# AS3364_DG412_bus_mixer_v1_0_copy.net
KiCad netlist of a schematic drawn in EAGLE
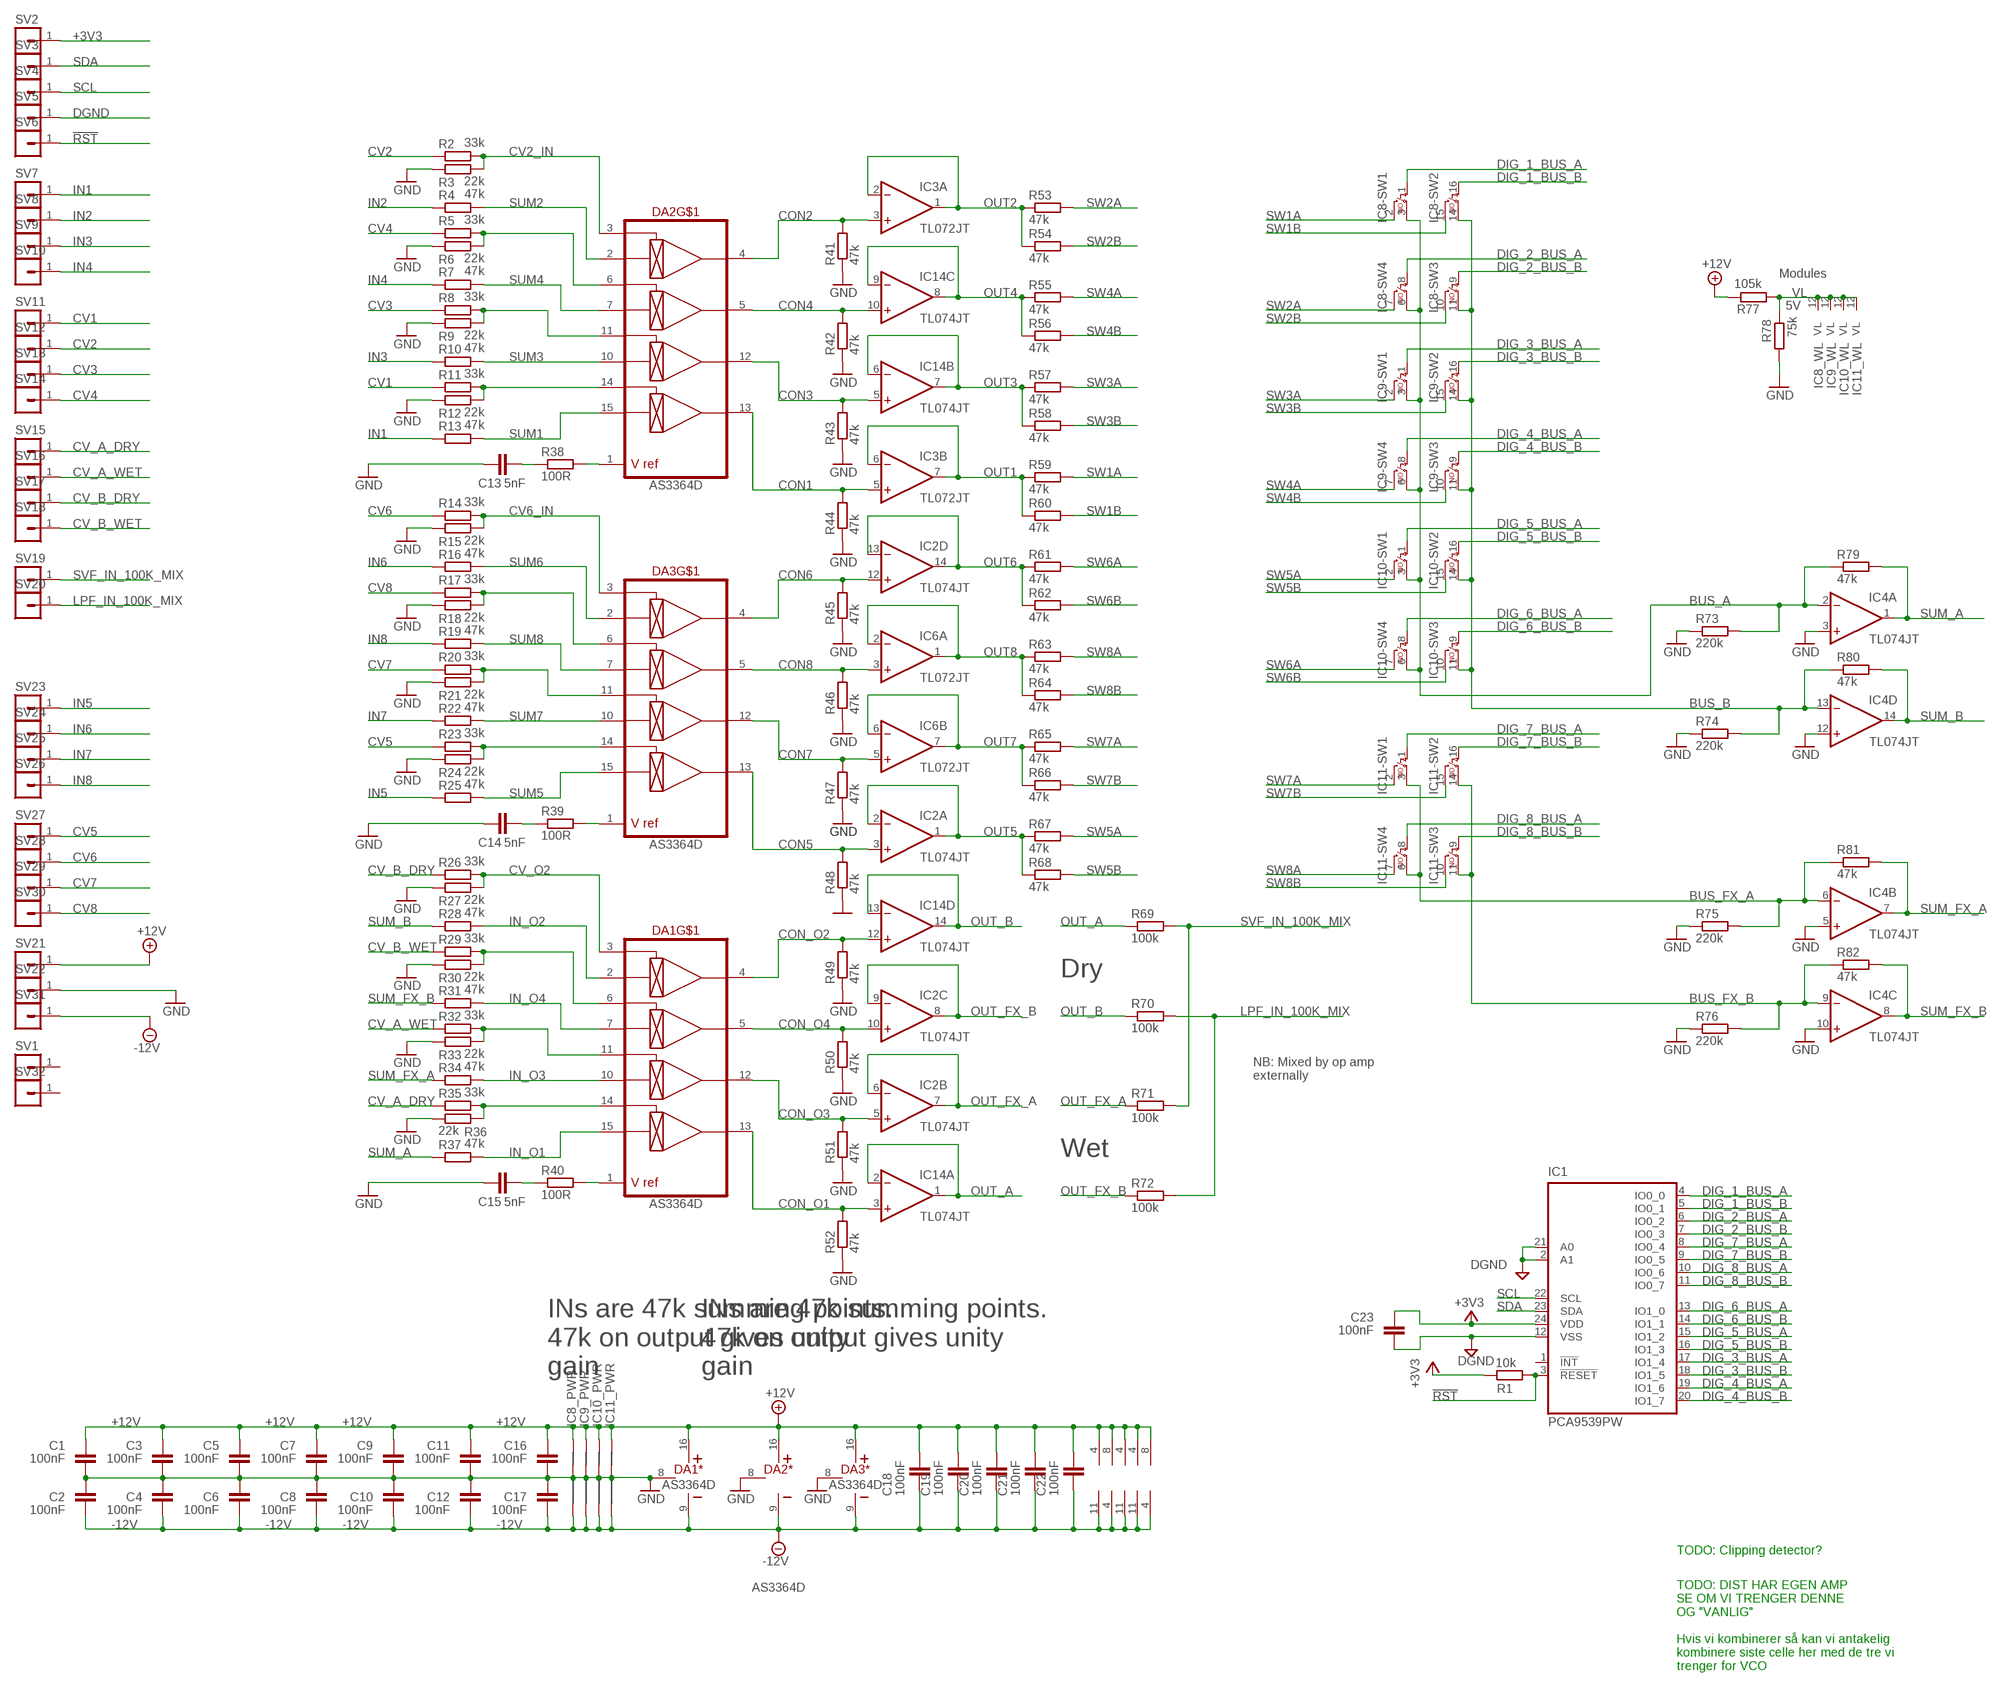
[diagram p0: schematic, sheet 1]

(export (version "E")
  (design (tool "Eeschema 10.0.6"))
  (components
    (comp (ref "C1")
      (value "100nF")
      (footprint "eagle-import:C0402")
      (libsource (lib "eagle-import") (part "C-EUC0402"))
    )
    (comp (ref "C2")
      (value "100nF")
      (footprint "eagle-import:C0402")
      (libsource (lib "eagle-import") (part "C-EUC0402"))
    )
    (comp (ref "C3")
      (value "100nF")
      (footprint "eagle-import:C0402")
      (libsource (lib "eagle-import") (part "C-EUC0402"))
    )
    (comp (ref "C4")
      (value "100nF")
      (footprint "eagle-import:C0402")
      (libsource (lib "eagle-import") (part "C-EUC0402"))
    )
    (comp (ref "C5")
      (value "100nF")
      (footprint "eagle-import:C0402")
      (libsource (lib "eagle-import") (part "C-EUC0402"))
    )
    (comp (ref "C6")
      (value "100nF")
      (footprint "eagle-import:C0402")
      (libsource (lib "eagle-import") (part "C-EUC0402"))
    )
    (comp (ref "C7")
      (value "100nF")
      (footprint "eagle-import:C0402")
      (libsource (lib "eagle-import") (part "C-EUC0402"))
    )
    (comp (ref "C8")
      (value "100nF")
      (footprint "eagle-import:C0402")
      (libsource (lib "eagle-import") (part "C-EUC0402"))
    )
    (comp (ref "C9")
      (value "100nF")
      (footprint "eagle-import:C0402")
      (libsource (lib "eagle-import") (part "C-EUC0402"))
    )
    (comp (ref "C10")
      (value "100nF")
      (footprint "eagle-import:C0402")
      (libsource (lib "eagle-import") (part "C-EUC0402"))
    )
    (comp (ref "C11")
      (value "100nF")
      (footprint "eagle-import:C0402")
      (libsource (lib "eagle-import") (part "C-EUC0402"))
    )
    (comp (ref "C12")
      (value "100nF")
      (footprint "eagle-import:C0402")
      (libsource (lib "eagle-import") (part "C-EUC0402"))
    )
    (comp (ref "C13")
      (value "5nF")
      (footprint "eagle-import:C0402")
      (libsource (lib "eagle-import") (part "C-EUC0402"))
    )
    (comp (ref "C14")
      (value "5nF")
      (footprint "eagle-import:C0402")
      (libsource (lib "eagle-import") (part "C-EUC0402"))
    )
    (comp (ref "C15")
      (value "5nF")
      (footprint "eagle-import:C0402")
      (libsource (lib "eagle-import") (part "C-EUC0402"))
    )
    (comp (ref "C16")
      (value "100nF")
      (footprint "eagle-import:C0402")
      (libsource (lib "eagle-import") (part "C-EUC0402"))
    )
    (comp (ref "C17")
      (value "100nF")
      (footprint "eagle-import:C0402")
      (libsource (lib "eagle-import") (part "C-EUC0402"))
    )
    (comp (ref "C18")
      (value "100nF")
      (footprint "eagle-import:C0402")
      (libsource (lib "eagle-import") (part "C-EUC0402"))
    )
    (comp (ref "C19")
      (value "100nF")
      (footprint "eagle-import:C0402")
      (libsource (lib "eagle-import") (part "C-EUC0402"))
    )
    (comp (ref "C20")
      (value "100nF")
      (footprint "eagle-import:C0402")
      (libsource (lib "eagle-import") (part "C-EUC0402"))
    )
    (comp (ref "C21")
      (value "100nF")
      (footprint "eagle-import:C0402")
      (libsource (lib "eagle-import") (part "C-EUC0402"))
    )
    (comp (ref "C22")
      (value "100nF")
      (footprint "eagle-import:C0402")
      (libsource (lib "eagle-import") (part "C-EUC0402"))
    )
    (comp (ref "C23")
      (value "100nF")
      (footprint "eagle-import:C0402")
      (libsource (lib "eagle-import") (part "C-EUC0402"))
    )
    (comp (ref "DA1")
      (value "AS3364D")
      (footprint "eagle-import:DIL16J")
      (libsource (lib "eagle-import") (part "AS3364D"))
    )
    (comp (ref "DA2")
      (value "AS3364D")
      (footprint "eagle-import:DIL16J")
      (libsource (lib "eagle-import") (part "AS3364D"))
    )
    (comp (ref "DA3")
      (value "AS3364D")
      (footprint "eagle-import:DIL16J")
      (libsource (lib "eagle-import") (part "AS3364D"))
    )
    (comp (ref "IC1")
      (value "PCA9539PW")
      (footprint "eagle-import:TSSOP24J")
      (libsource (lib "eagle-import") (part "PCA9539PW"))
    )
    (comp (ref "IC2")
      (value "TL074JT")
      (footprint "eagle-import:TSSOP14J")
      (libsource (lib "eagle-import") (part "TL074JT"))
    )
    (comp (ref "IC3")
      (value "TL072JT")
      (footprint "eagle-import:TSSOP8J")
      (libsource (lib "eagle-import") (part "TL072JT"))
    )
    (comp (ref "IC4")
      (value "TL074JT")
      (footprint "eagle-import:TSSOP14J")
      (libsource (lib "eagle-import") (part "TL074JT"))
    )
    (comp (ref "IC6")
      (value "TL072JT")
      (footprint "eagle-import:TSSOP8J")
      (libsource (lib "eagle-import") (part "TL072JT"))
    )
    (comp (ref "IC8")
      (value "DG412-J")
      (footprint "eagle-import:DIL16J")
      (libsource (lib "eagle-import") (part "DG412-J"))
    )
    (comp (ref "IC9")
      (value "DG412-J")
      (footprint "eagle-import:DIL16J")
      (libsource (lib "eagle-import") (part "DG412-J"))
    )
    (comp (ref "IC10")
      (value "DG412-J")
      (footprint "eagle-import:DIL16J")
      (libsource (lib "eagle-import") (part "DG412-J"))
    )
    (comp (ref "IC11")
      (value "DG412-J")
      (footprint "eagle-import:DIL16J")
      (libsource (lib "eagle-import") (part "DG412-J"))
    )
    (comp (ref "IC14")
      (value "TL074JT")
      (footprint "eagle-import:TSSOP14J")
      (libsource (lib "eagle-import") (part "TL074JT"))
    )
    (comp (ref "R1")
      (value "10k")
      (footprint "eagle-import:R0402")
      (libsource (lib "eagle-import") (part "R-EU_R0402"))
    )
    (comp (ref "R2")
      (value "33k")
      (footprint "eagle-import:R0402")
      (libsource (lib "eagle-import") (part "R-EU_R0402"))
    )
    (comp (ref "R3")
      (value "22k")
      (footprint "eagle-import:R0402")
      (libsource (lib "eagle-import") (part "R-EU_R0402"))
    )
    (comp (ref "R4")
      (value "47k")
      (footprint "eagle-import:R0402")
      (libsource (lib "eagle-import") (part "R-EU_R0402"))
    )
    (comp (ref "R5")
      (value "33k")
      (footprint "eagle-import:R0402")
      (libsource (lib "eagle-import") (part "R-EU_R0402"))
    )
    (comp (ref "R6")
      (value "22k")
      (footprint "eagle-import:R0402")
      (libsource (lib "eagle-import") (part "R-EU_R0402"))
    )
    (comp (ref "R7")
      (value "47k")
      (footprint "eagle-import:R0402")
      (libsource (lib "eagle-import") (part "R-EU_R0402"))
    )
    (comp (ref "R8")
      (value "33k")
      (footprint "eagle-import:R0402")
      (libsource (lib "eagle-import") (part "R-EU_R0402"))
    )
    (comp (ref "R9")
      (value "22k")
      (footprint "eagle-import:R0402")
      (libsource (lib "eagle-import") (part "R-EU_R0402"))
    )
    (comp (ref "R10")
      (value "47k")
      (footprint "eagle-import:R0402")
      (libsource (lib "eagle-import") (part "R-EU_R0402"))
    )
    (comp (ref "R11")
      (value "33k")
      (footprint "eagle-import:R0402")
      (libsource (lib "eagle-import") (part "R-EU_R0402"))
    )
    (comp (ref "R12")
      (value "22k")
      (footprint "eagle-import:R0402")
      (libsource (lib "eagle-import") (part "R-EU_R0402"))
    )
    (comp (ref "R13")
      (value "47k")
      (footprint "eagle-import:R0402")
      (libsource (lib "eagle-import") (part "R-EU_R0402"))
    )
    (comp (ref "R14")
      (value "33k")
      (footprint "eagle-import:R0402")
      (libsource (lib "eagle-import") (part "R-EU_R0402"))
    )
    (comp (ref "R15")
      (value "22k")
      (footprint "eagle-import:R0402")
      (libsource (lib "eagle-import") (part "R-EU_R0402"))
    )
    (comp (ref "R16")
      (value "47k")
      (footprint "eagle-import:R0402")
      (libsource (lib "eagle-import") (part "R-EU_R0402"))
    )
    (comp (ref "R17")
      (value "33k")
      (footprint "eagle-import:R0402")
      (libsource (lib "eagle-import") (part "R-EU_R0402"))
    )
    (comp (ref "R18")
      (value "22k")
      (footprint "eagle-import:R0402")
      (libsource (lib "eagle-import") (part "R-EU_R0402"))
    )
    (comp (ref "R19")
      (value "47k")
      (footprint "eagle-import:R0402")
      (libsource (lib "eagle-import") (part "R-EU_R0402"))
    )
    (comp (ref "R20")
      (value "33k")
      (footprint "eagle-import:R0402")
      (libsource (lib "eagle-import") (part "R-EU_R0402"))
    )
    (comp (ref "R21")
      (value "22k")
      (footprint "eagle-import:R0402")
      (libsource (lib "eagle-import") (part "R-EU_R0402"))
    )
    (comp (ref "R22")
      (value "47k")
      (footprint "eagle-import:R0402")
      (libsource (lib "eagle-import") (part "R-EU_R0402"))
    )
    (comp (ref "R23")
      (value "33k")
      (footprint "eagle-import:R0402")
      (libsource (lib "eagle-import") (part "R-EU_R0402"))
    )
    (comp (ref "R24")
      (value "22k")
      (footprint "eagle-import:R0402")
      (libsource (lib "eagle-import") (part "R-EU_R0402"))
    )
    (comp (ref "R25")
      (value "47k")
      (footprint "eagle-import:R0402")
      (libsource (lib "eagle-import") (part "R-EU_R0402"))
    )
    (comp (ref "R26")
      (value "33k")
      (footprint "eagle-import:R0402")
      (libsource (lib "eagle-import") (part "R-EU_R0402"))
    )
    (comp (ref "R27")
      (value "22k")
      (footprint "eagle-import:R0402")
      (libsource (lib "eagle-import") (part "R-EU_R0402"))
    )
    (comp (ref "R28")
      (value "47k")
      (footprint "eagle-import:R0402")
      (libsource (lib "eagle-import") (part "R-EU_R0402"))
    )
    (comp (ref "R29")
      (value "33k")
      (footprint "eagle-import:R0402")
      (libsource (lib "eagle-import") (part "R-EU_R0402"))
    )
    (comp (ref "R30")
      (value "22k")
      (footprint "eagle-import:R0402")
      (libsource (lib "eagle-import") (part "R-EU_R0402"))
    )
    (comp (ref "R31")
      (value "47k")
      (footprint "eagle-import:R0402")
      (libsource (lib "eagle-import") (part "R-EU_R0402"))
    )
    (comp (ref "R32")
      (value "33k")
      (footprint "eagle-import:R0402")
      (libsource (lib "eagle-import") (part "R-EU_R0402"))
    )
    (comp (ref "R33")
      (value "22k")
      (footprint "eagle-import:R0402")
      (libsource (lib "eagle-import") (part "R-EU_R0402"))
    )
    (comp (ref "R34")
      (value "47k")
      (footprint "eagle-import:R0402")
      (libsource (lib "eagle-import") (part "R-EU_R0402"))
    )
    (comp (ref "R35")
      (value "33k")
      (footprint "eagle-import:R0402")
      (libsource (lib "eagle-import") (part "R-EU_R0402"))
    )
    (comp (ref "R36")
      (value "22k")
      (footprint "eagle-import:R0402")
      (libsource (lib "eagle-import") (part "R-EU_R0402"))
    )
    (comp (ref "R37")
      (value "47k")
      (footprint "eagle-import:R0402")
      (libsource (lib "eagle-import") (part "R-EU_R0402"))
    )
    (comp (ref "R38")
      (value "100R")
      (footprint "eagle-import:R0402")
      (libsource (lib "eagle-import") (part "R-EU_R0402"))
    )
    (comp (ref "R39")
      (value "100R")
      (footprint "eagle-import:R0402")
      (libsource (lib "eagle-import") (part "R-EU_R0402"))
    )
    (comp (ref "R40")
      (value "100R")
      (footprint "eagle-import:R0402")
      (libsource (lib "eagle-import") (part "R-EU_R0402"))
    )
    (comp (ref "R41")
      (value "47k")
      (footprint "eagle-import:R0402")
      (libsource (lib "eagle-import") (part "R-EU_R0402"))
    )
    (comp (ref "R42")
      (value "47k")
      (footprint "eagle-import:R0402")
      (libsource (lib "eagle-import") (part "R-EU_R0402"))
    )
    (comp (ref "R43")
      (value "47k")
      (footprint "eagle-import:R0402")
      (libsource (lib "eagle-import") (part "R-EU_R0402"))
    )
    (comp (ref "R44")
      (value "47k")
      (footprint "eagle-import:R0402")
      (libsource (lib "eagle-import") (part "R-EU_R0402"))
    )
    (comp (ref "R45")
      (value "47k")
      (footprint "eagle-import:R0402")
      (libsource (lib "eagle-import") (part "R-EU_R0402"))
    )
    (comp (ref "R46")
      (value "47k")
      (footprint "eagle-import:R0402")
      (libsource (lib "eagle-import") (part "R-EU_R0402"))
    )
    (comp (ref "R47")
      (value "47k")
      (footprint "eagle-import:R0402")
      (libsource (lib "eagle-import") (part "R-EU_R0402"))
    )
    (comp (ref "R48")
      (value "47k")
      (footprint "eagle-import:R0402")
      (libsource (lib "eagle-import") (part "R-EU_R0402"))
    )
    (comp (ref "R49")
      (value "47k")
      (footprint "eagle-import:R0402")
      (libsource (lib "eagle-import") (part "R-EU_R0402"))
    )
    (comp (ref "R50")
      (value "47k")
      (footprint "eagle-import:R0402")
      (libsource (lib "eagle-import") (part "R-EU_R0402"))
    )
    (comp (ref "R51")
      (value "47k")
      (footprint "eagle-import:R0402")
      (libsource (lib "eagle-import") (part "R-EU_R0402"))
    )
    (comp (ref "R52")
      (value "47k")
      (footprint "eagle-import:R0402")
      (libsource (lib "eagle-import") (part "R-EU_R0402"))
    )
    (comp (ref "R53")
      (value "47k")
      (footprint "eagle-import:R0402")
      (libsource (lib "eagle-import") (part "R-EU_R0402"))
    )
    (comp (ref "R54")
      (value "47k")
      (footprint "eagle-import:R0402")
      (libsource (lib "eagle-import") (part "R-EU_R0402"))
    )
    (comp (ref "R55")
      (value "47k")
      (footprint "eagle-import:R0402")
      (libsource (lib "eagle-import") (part "R-EU_R0402"))
    )
    (comp (ref "R56")
      (value "47k")
      (footprint "eagle-import:R0402")
      (libsource (lib "eagle-import") (part "R-EU_R0402"))
    )
    (comp (ref "R57")
      (value "47k")
      (footprint "eagle-import:R0402")
      (libsource (lib "eagle-import") (part "R-EU_R0402"))
    )
    (comp (ref "R58")
      (value "47k")
      (footprint "eagle-import:R0402")
      (libsource (lib "eagle-import") (part "R-EU_R0402"))
    )
    (comp (ref "R59")
      (value "47k")
      (footprint "eagle-import:R0402")
      (libsource (lib "eagle-import") (part "R-EU_R0402"))
    )
    (comp (ref "R60")
      (value "47k")
      (footprint "eagle-import:R0402")
      (libsource (lib "eagle-import") (part "R-EU_R0402"))
    )
    (comp (ref "R61")
      (value "47k")
      (footprint "eagle-import:R0402")
      (libsource (lib "eagle-import") (part "R-EU_R0402"))
    )
    (comp (ref "R62")
      (value "47k")
      (footprint "eagle-import:R0402")
      (libsource (lib "eagle-import") (part "R-EU_R0402"))
    )
    (comp (ref "R63")
      (value "47k")
      (footprint "eagle-import:R0402")
      (libsource (lib "eagle-import") (part "R-EU_R0402"))
    )
    (comp (ref "R64")
      (value "47k")
      (footprint "eagle-import:R0402")
      (libsource (lib "eagle-import") (part "R-EU_R0402"))
    )
    (comp (ref "R65")
      (value "47k")
      (footprint "eagle-import:R0402")
      (libsource (lib "eagle-import") (part "R-EU_R0402"))
    )
    (comp (ref "R66")
      (value "47k")
      (footprint "eagle-import:R0402")
      (libsource (lib "eagle-import") (part "R-EU_R0402"))
    )
    (comp (ref "R67")
      (value "47k")
      (footprint "eagle-import:R0402")
      (libsource (lib "eagle-import") (part "R-EU_R0402"))
    )
    (comp (ref "R68")
      (value "47k")
      (footprint "eagle-import:R0402")
      (libsource (lib "eagle-import") (part "R-EU_R0402"))
    )
    (comp (ref "R69")
      (value "100k")
      (footprint "eagle-import:R0402")
      (libsource (lib "eagle-import") (part "R-EU_R0402"))
    )
    (comp (ref "R70")
      (value "100k")
      (footprint "eagle-import:R0402")
      (libsource (lib "eagle-import") (part "R-EU_R0402"))
    )
    (comp (ref "R71")
      (value "100k")
      (footprint "eagle-import:R0402")
      (libsource (lib "eagle-import") (part "R-EU_R0402"))
    )
    (comp (ref "R72")
      (value "100k")
      (footprint "eagle-import:R0402")
      (libsource (lib "eagle-import") (part "R-EU_R0402"))
    )
    (comp (ref "R73")
      (value "220k")
      (footprint "eagle-import:R0402")
      (libsource (lib "eagle-import") (part "R-EU_R0402"))
    )
    (comp (ref "R74")
      (value "220k")
      (footprint "eagle-import:R0402")
      (libsource (lib "eagle-import") (part "R-EU_R0402"))
    )
    (comp (ref "R75")
      (value "220k")
      (footprint "eagle-import:R0402")
      (libsource (lib "eagle-import") (part "R-EU_R0402"))
    )
    (comp (ref "R76")
      (value "220k")
      (footprint "eagle-import:R0402")
      (libsource (lib "eagle-import") (part "R-EU_R0402"))
    )
    (comp (ref "R77")
      (value "105k")
      (footprint "eagle-import:R0402")
      (libsource (lib "eagle-import") (part "R-EU_R0402"))
    )
    (comp (ref "R78")
      (value "75k")
      (footprint "eagle-import:R0402")
      (libsource (lib "eagle-import") (part "R-EU_R0402"))
    )
    (comp (ref "R79")
      (value "47k")
      (footprint "eagle-import:R0402")
      (libsource (lib "eagle-import") (part "R-EU_R0402"))
    )
    (comp (ref "R80")
      (value "47k")
      (footprint "eagle-import:R0402")
      (libsource (lib "eagle-import") (part "R-EU_R0402"))
    )
    (comp (ref "R81")
      (value "47k")
      (footprint "eagle-import:R0402")
      (libsource (lib "eagle-import") (part "R-EU_R0402"))
    )
    (comp (ref "R82")
      (value "47k")
      (footprint "eagle-import:R0402")
      (libsource (lib "eagle-import") (part "R-EU_R0402"))
    )
    (comp (ref "SV1")
      (value "MA01-1JP")
      (footprint "eagle-import:SIP-PIN01-1J")
      (libsource (lib "eagle-import") (part "MA01-1JP"))
    )
    (comp (ref "SV2")
      (value "MA01-1JP")
      (footprint "eagle-import:SIP-PIN01-1J")
      (libsource (lib "eagle-import") (part "MA01-1JP"))
    )
    (comp (ref "SV3")
      (value "MA01-1JP")
      (footprint "eagle-import:SIP-PIN01-1J")
      (libsource (lib "eagle-import") (part "MA01-1JP"))
    )
    (comp (ref "SV4")
      (value "MA01-1JP")
      (footprint "eagle-import:SIP-PIN01-1J")
      (libsource (lib "eagle-import") (part "MA01-1JP"))
    )
    (comp (ref "SV5")
      (value "MA01-1JP")
      (footprint "eagle-import:SIP-PIN01-1J")
      (libsource (lib "eagle-import") (part "MA01-1JP"))
    )
    (comp (ref "SV6")
      (value "MA01-1JP")
      (footprint "eagle-import:SIP-PIN01-1J")
      (libsource (lib "eagle-import") (part "MA01-1JP"))
    )
    (comp (ref "SV7")
      (value "MA01-1JP")
      (footprint "eagle-import:SIP-PIN01-1J")
      (libsource (lib "eagle-import") (part "MA01-1JP"))
    )
    (comp (ref "SV8")
      (value "MA01-1JP")
      (footprint "eagle-import:SIP-PIN01-1J")
      (libsource (lib "eagle-import") (part "MA01-1JP"))
    )
    (comp (ref "SV9")
      (value "MA01-1JP")
      (footprint "eagle-import:SIP-PIN01-1J")
      (libsource (lib "eagle-import") (part "MA01-1JP"))
    )
    (comp (ref "SV10")
      (value "MA01-1JP")
      (footprint "eagle-import:SIP-PIN01-1J")
      (libsource (lib "eagle-import") (part "MA01-1JP"))
    )
    (comp (ref "SV11")
      (value "MA01-1JP")
      (footprint "eagle-import:SIP-PIN01-1J")
      (libsource (lib "eagle-import") (part "MA01-1JP"))
    )
    (comp (ref "SV12")
      (value "MA01-1JP")
      (footprint "eagle-import:SIP-PIN01-1J")
      (libsource (lib "eagle-import") (part "MA01-1JP"))
    )
    (comp (ref "SV13")
      (value "MA01-1JP")
      (footprint "eagle-import:SIP-PIN01-1J")
      (libsource (lib "eagle-import") (part "MA01-1JP"))
    )
    (comp (ref "SV14")
      (value "MA01-1JP")
      (footprint "eagle-import:SIP-PIN01-1J")
      (libsource (lib "eagle-import") (part "MA01-1JP"))
    )
    (comp (ref "SV15")
      (value "MA01-1JP")
      (footprint "eagle-import:SIP-PIN01-1J")
      (libsource (lib "eagle-import") (part "MA01-1JP"))
    )
    (comp (ref "SV16")
      (value "MA01-1JP")
      (footprint "eagle-import:SIP-PIN01-1J")
      (libsource (lib "eagle-import") (part "MA01-1JP"))
    )
    (comp (ref "SV17")
      (value "MA01-1JP")
      (footprint "eagle-import:SIP-PIN01-1J")
      (libsource (lib "eagle-import") (part "MA01-1JP"))
    )
    (comp (ref "SV18")
      (value "MA01-1JP")
      (footprint "eagle-import:SIP-PIN01-1J")
      (libsource (lib "eagle-import") (part "MA01-1JP"))
    )
    (comp (ref "SV19")
      (value "MA01-1JP")
      (footprint "eagle-import:SIP-PIN01-1J")
      (libsource (lib "eagle-import") (part "MA01-1JP"))
    )
    (comp (ref "SV20")
      (value "MA01-1JP")
      (footprint "eagle-import:SIP-PIN01-1J")
      (libsource (lib "eagle-import") (part "MA01-1JP"))
    )
    (comp (ref "SV21")
      (value "MA01-1JP")
      (footprint "eagle-import:SIP-PIN01-1J")
      (libsource (lib "eagle-import") (part "MA01-1JP"))
    )
    (comp (ref "SV22")
      (value "MA01-1JP")
      (footprint "eagle-import:SIP-PIN01-1J")
      (libsource (lib "eagle-import") (part "MA01-1JP"))
    )
    (comp (ref "SV23")
      (value "MA01-1JP")
      (footprint "eagle-import:SIP-PIN01-1J")
      (libsource (lib "eagle-import") (part "MA01-1JP"))
    )
    (comp (ref "SV24")
      (value "MA01-1JP")
      (footprint "eagle-import:SIP-PIN01-1J")
      (libsource (lib "eagle-import") (part "MA01-1JP"))
    )
    (comp (ref "SV25")
      (value "MA01-1JP")
      (footprint "eagle-import:SIP-PIN01-1J")
      (libsource (lib "eagle-import") (part "MA01-1JP"))
    )
    (comp (ref "SV26")
      (value "MA01-1JP")
      (footprint "eagle-import:SIP-PIN01-1J")
      (libsource (lib "eagle-import") (part "MA01-1JP"))
    )
    (comp (ref "SV27")
      (value "MA01-1JP")
      (footprint "eagle-import:SIP-PIN01-1J")
      (libsource (lib "eagle-import") (part "MA01-1JP"))
    )
    (comp (ref "SV28")
      (value "MA01-1JP")
      (footprint "eagle-import:SIP-PIN01-1J")
      (libsource (lib "eagle-import") (part "MA01-1JP"))
    )
    (comp (ref "SV29")
      (value "MA01-1JP")
      (footprint "eagle-import:SIP-PIN01-1J")
      (libsource (lib "eagle-import") (part "MA01-1JP"))
    )
    (comp (ref "SV30")
      (value "MA01-1JP")
      (footprint "eagle-import:SIP-PIN01-1J")
      (libsource (lib "eagle-import") (part "MA01-1JP"))
    )
    (comp (ref "SV31")
      (value "MA01-1JP")
      (footprint "eagle-import:SIP-PIN01-1J")
      (libsource (lib "eagle-import") (part "MA01-1JP"))
    )
    (comp (ref "SV32")
      (value "MA01-1JP")
      (footprint "eagle-import:SIP-PIN01-1J")
      (libsource (lib "eagle-import") (part "MA01-1JP"))
    )
  )
  (nets
    (net (code "1") (name "+3V3") (class "Default")
      (node (ref "C23") (pin "2") (pinfunction "2_2") (pintype "passive"))
      (node (ref "IC1") (pin "24") (pinfunction "VDD_24") (pintype "power_in"))
      (node (ref "R1") (pin "1") (pinfunction "1_1") (pintype "passive"))
      (node (ref "SV2") (pin "1") (pinfunction "1_1") (pintype "passive"))
    )
    (net (code "2") (name "+12V") (class "Default")
      (node (ref "C1") (pin "2") (pinfunction "2_2") (pintype "passive"))
      (node (ref "C11") (pin "2") (pinfunction "2_2") (pintype "passive"))
      (node (ref "C16") (pin "2") (pinfunction "2_2") (pintype "passive"))
      (node (ref "C18") (pin "2") (pinfunction "2_2") (pintype "passive"))
      (node (ref "C19") (pin "2") (pinfunction "2_2") (pintype "passive"))
      (node (ref "C20") (pin "2") (pinfunction "2_2") (pintype "passive"))
      (node (ref "C21") (pin "2") (pinfunction "2_2") (pintype "passive"))
      (node (ref "C22") (pin "2") (pinfunction "2_2") (pintype "passive"))
      (node (ref "C3") (pin "2") (pinfunction "2_2") (pintype "passive"))
      (node (ref "C5") (pin "2") (pinfunction "2_2") (pintype "passive"))
      (node (ref "C7") (pin "2") (pinfunction "2_2") (pintype "passive"))
      (node (ref "C9") (pin "2") (pinfunction "2_2") (pintype "passive"))
      (node (ref "DA1") (pin "16") (pinfunction "V+_16") (pintype "power_in"))
      (node (ref "DA2") (pin "16") (pinfunction "V+_16") (pintype "power_in"))
      (node (ref "DA3") (pin "16") (pinfunction "V+_16") (pintype "power_in"))
      (node (ref "IC10") (pin "13") (pinfunction "+15V_13") (pintype "power_in"))
      (node (ref "IC11") (pin "13") (pinfunction "+15V_13") (pintype "power_in"))
      (node (ref "IC14") (pin "4") (pinfunction "V+_4") (pintype "power_in"))
      (node (ref "IC2") (pin "4") (pinfunction "V+_4") (pintype "power_in"))
      (node (ref "IC3") (pin "8") (pinfunction "V+_8") (pintype "power_in"))
      (node (ref "IC4") (pin "4") (pinfunction "V+_4") (pintype "power_in"))
      (node (ref "IC6") (pin "8") (pinfunction "V+_8") (pintype "power_in"))
      (node (ref "IC8") (pin "13") (pinfunction "+15V_13") (pintype "power_in"))
      (node (ref "IC9") (pin "13") (pinfunction "+15V_13") (pintype "power_in"))
      (node (ref "R77") (pin "1") (pinfunction "1_1") (pintype "passive"))
      (node (ref "SV21") (pin "1") (pinfunction "1_1") (pintype "passive"))
    )
    (net (code "3") (name "-12V") (class "Default")
      (node (ref "C10") (pin "1") (pinfunction "1_1") (pintype "passive"))
      (node (ref "C12") (pin "1") (pinfunction "1_1") (pintype "passive"))
      (node (ref "C17") (pin "1") (pinfunction "1_1") (pintype "passive"))
      (node (ref "C18") (pin "1") (pinfunction "1_1") (pintype "passive"))
      (node (ref "C19") (pin "1") (pinfunction "1_1") (pintype "passive"))
      (node (ref "C2") (pin "1") (pinfunction "1_1") (pintype "passive"))
      (node (ref "C20") (pin "1") (pinfunction "1_1") (pintype "passive"))
      (node (ref "C21") (pin "1") (pinfunction "1_1") (pintype "passive"))
      (node (ref "C22") (pin "1") (pinfunction "1_1") (pintype "passive"))
      (node (ref "C4") (pin "1") (pinfunction "1_1") (pintype "passive"))
      (node (ref "C6") (pin "1") (pinfunction "1_1") (pintype "passive"))
      (node (ref "C8") (pin "1") (pinfunction "1_1") (pintype "passive"))
      (node (ref "DA1") (pin "9") (pinfunction "V-_9") (pintype "power_in"))
      (node (ref "DA2") (pin "9") (pinfunction "V-_9") (pintype "power_in"))
      (node (ref "DA3") (pin "9") (pinfunction "V-_9") (pintype "power_in"))
      (node (ref "IC10") (pin "4") (pinfunction "-15V_4") (pintype "power_in"))
      (node (ref "IC11") (pin "4") (pinfunction "-15V_4") (pintype "power_in"))
      (node (ref "IC14") (pin "11") (pinfunction "V-_11") (pintype "power_in"))
      (node (ref "IC2") (pin "11") (pinfunction "V-_11") (pintype "power_in"))
      (node (ref "IC3") (pin "4") (pinfunction "V-_4") (pintype "power_in"))
      (node (ref "IC4") (pin "11") (pinfunction "V-_11") (pintype "power_in"))
      (node (ref "IC6") (pin "4") (pinfunction "V-_4") (pintype "power_in"))
      (node (ref "IC8") (pin "4") (pinfunction "-15V_4") (pintype "power_in"))
      (node (ref "IC9") (pin "4") (pinfunction "-15V_4") (pintype "power_in"))
      (node (ref "SV31") (pin "1") (pinfunction "1_1") (pintype "passive"))
    )
    (net (code "4") (name "/BUS_A") (class "Default")
      (node (ref "IC10") (pin "3") (pinfunction "S_3") (pintype "bidirectional"))
      (node (ref "IC10") (pin "6") (pinfunction "S_6") (pintype "bidirectional"))
      (node (ref "IC4") (pin "2") (pinfunction "-IN_2") (pintype "input"))
      (node (ref "IC8") (pin "3") (pinfunction "S_3") (pintype "bidirectional"))
      (node (ref "IC8") (pin "6") (pinfunction "S_6") (pintype "bidirectional"))
      (node (ref "IC9") (pin "3") (pinfunction "S_3") (pintype "bidirectional"))
      (node (ref "IC9") (pin "6") (pinfunction "S_6") (pintype "bidirectional"))
      (node (ref "R73") (pin "2") (pinfunction "2_2") (pintype "passive"))
      (node (ref "R79") (pin "1") (pinfunction "1_1") (pintype "passive"))
    )
    (net (code "5") (name "/BUS_B") (class "Default")
      (node (ref "IC10") (pin "11") (pinfunction "S_11") (pintype "bidirectional"))
      (node (ref "IC10") (pin "14") (pinfunction "S_14") (pintype "bidirectional"))
      (node (ref "IC4") (pin "13") (pinfunction "-IN_13") (pintype "input"))
      (node (ref "IC8") (pin "11") (pinfunction "S_11") (pintype "bidirectional"))
      (node (ref "IC8") (pin "14") (pinfunction "S_14") (pintype "bidirectional"))
      (node (ref "IC9") (pin "11") (pinfunction "S_11") (pintype "bidirectional"))
      (node (ref "IC9") (pin "14") (pinfunction "S_14") (pintype "bidirectional"))
      (node (ref "R74") (pin "2") (pinfunction "2_2") (pintype "passive"))
      (node (ref "R80") (pin "1") (pinfunction "1_1") (pintype "passive"))
    )
    (net (code "6") (name "/BUS_FX_A") (class "Default")
      (node (ref "IC11") (pin "3") (pinfunction "S_3") (pintype "bidirectional"))
      (node (ref "IC11") (pin "6") (pinfunction "S_6") (pintype "bidirectional"))
      (node (ref "IC4") (pin "6") (pinfunction "-IN_6") (pintype "input"))
      (node (ref "R75") (pin "2") (pinfunction "2_2") (pintype "passive"))
      (node (ref "R81") (pin "1") (pinfunction "1_1") (pintype "passive"))
    )
    (net (code "7") (name "/BUS_FX_B") (class "Default")
      (node (ref "IC11") (pin "11") (pinfunction "S_11") (pintype "bidirectional"))
      (node (ref "IC11") (pin "14") (pinfunction "S_14") (pintype "bidirectional"))
      (node (ref "IC4") (pin "9") (pinfunction "-IN_9") (pintype "input"))
      (node (ref "R76") (pin "2") (pinfunction "2_2") (pintype "passive"))
      (node (ref "R82") (pin "1") (pinfunction "1_1") (pintype "passive"))
    )
    (net (code "8") (name "/CON1") (class "Default")
      (node (ref "DA2") (pin "13") (pinfunction "OUT4_13") (pintype "output"))
      (node (ref "IC3") (pin "5") (pinfunction "+IN_5") (pintype "input"))
      (node (ref "R44") (pin "2") (pinfunction "2_2") (pintype "passive"))
    )
    (net (code "9") (name "/CON2") (class "Default")
      (node (ref "DA2") (pin "4") (pinfunction "OUT1_4") (pintype "output"))
      (node (ref "IC3") (pin "3") (pinfunction "+IN_3") (pintype "input"))
      (node (ref "R41") (pin "2") (pinfunction "2_2") (pintype "passive"))
    )
    (net (code "10") (name "/CON3") (class "Default")
      (node (ref "DA2") (pin "12") (pinfunction "OUT3_12") (pintype "output"))
      (node (ref "IC14") (pin "5") (pinfunction "+IN_5") (pintype "input"))
      (node (ref "R43") (pin "2") (pinfunction "2_2") (pintype "passive"))
    )
    (net (code "11") (name "/CON4") (class "Default")
      (node (ref "DA2") (pin "5") (pinfunction "OUT2_5") (pintype "output"))
      (node (ref "IC14") (pin "10") (pinfunction "+IN_10") (pintype "input"))
      (node (ref "R42") (pin "2") (pinfunction "2_2") (pintype "passive"))
    )
    (net (code "12") (name "/CON5") (class "Default")
      (node (ref "DA3") (pin "13") (pinfunction "OUT4_13") (pintype "output"))
      (node (ref "IC2") (pin "3") (pinfunction "+IN_3") (pintype "input"))
      (node (ref "R48") (pin "2") (pinfunction "2_2") (pintype "passive"))
    )
    (net (code "13") (name "/CON6") (class "Default")
      (node (ref "DA3") (pin "4") (pinfunction "OUT1_4") (pintype "output"))
      (node (ref "IC2") (pin "12") (pinfunction "+IN_12") (pintype "input"))
      (node (ref "R45") (pin "2") (pinfunction "2_2") (pintype "passive"))
    )
    (net (code "14") (name "/CON7") (class "Default")
      (node (ref "DA3") (pin "12") (pinfunction "OUT3_12") (pintype "output"))
      (node (ref "IC6") (pin "5") (pinfunction "+IN_5") (pintype "input"))
      (node (ref "R47") (pin "2") (pinfunction "2_2") (pintype "passive"))
    )
    (net (code "15") (name "/CON8") (class "Default")
      (node (ref "DA3") (pin "5") (pinfunction "OUT2_5") (pintype "output"))
      (node (ref "IC6") (pin "3") (pinfunction "+IN_3") (pintype "input"))
      (node (ref "R46") (pin "2") (pinfunction "2_2") (pintype "passive"))
    )
    (net (code "16") (name "/CON_O1") (class "Default")
      (node (ref "DA1") (pin "13") (pinfunction "OUT4_13") (pintype "output"))
      (node (ref "IC14") (pin "3") (pinfunction "+IN_3") (pintype "input"))
      (node (ref "R52") (pin "2") (pinfunction "2_2") (pintype "passive"))
    )
    (net (code "17") (name "/CON_O2") (class "Default")
      (node (ref "DA1") (pin "4") (pinfunction "OUT1_4") (pintype "output"))
      (node (ref "IC14") (pin "12") (pinfunction "+IN_12") (pintype "input"))
      (node (ref "R49") (pin "2") (pinfunction "2_2") (pintype "passive"))
    )
    (net (code "18") (name "/CON_O3") (class "Default")
      (node (ref "DA1") (pin "12") (pinfunction "OUT3_12") (pintype "output"))
      (node (ref "IC2") (pin "5") (pinfunction "+IN_5") (pintype "input"))
      (node (ref "R51") (pin "2") (pinfunction "2_2") (pintype "passive"))
    )
    (net (code "19") (name "/CON_O4") (class "Default")
      (node (ref "DA1") (pin "5") (pinfunction "OUT2_5") (pintype "output"))
      (node (ref "IC2") (pin "10") (pinfunction "+IN_10") (pintype "input"))
      (node (ref "R50") (pin "2") (pinfunction "2_2") (pintype "passive"))
    )
    (net (code "20") (name "/CV1") (class "Default")
      (node (ref "R11") (pin "1") (pinfunction "1_1") (pintype "passive"))
      (node (ref "SV11") (pin "1") (pinfunction "1_1") (pintype "passive"))
    )
    (net (code "21") (name "/CV2") (class "Default")
      (node (ref "R2") (pin "1") (pinfunction "1_1") (pintype "passive"))
      (node (ref "SV12") (pin "1") (pinfunction "1_1") (pintype "passive"))
    )
    (net (code "22") (name "/CV2_IN") (class "Default")
      (node (ref "DA2") (pin "3") (pinfunction "CV1_3") (pintype "input"))
      (node (ref "R2") (pin "2") (pinfunction "2_2") (pintype "passive"))
      (node (ref "R3") (pin "2") (pinfunction "2_2") (pintype "passive"))
    )
    (net (code "23") (name "/CV3") (class "Default")
      (node (ref "R8") (pin "1") (pinfunction "1_1") (pintype "passive"))
      (node (ref "SV13") (pin "1") (pinfunction "1_1") (pintype "passive"))
    )
    (net (code "24") (name "/CV4") (class "Default")
      (node (ref "R5") (pin "1") (pinfunction "1_1") (pintype "passive"))
      (node (ref "SV14") (pin "1") (pinfunction "1_1") (pintype "passive"))
    )
    (net (code "25") (name "/CV5") (class "Default")
      (node (ref "R23") (pin "1") (pinfunction "1_1") (pintype "passive"))
      (node (ref "SV27") (pin "1") (pinfunction "1_1") (pintype "passive"))
    )
    (net (code "26") (name "/CV6") (class "Default")
      (node (ref "R14") (pin "1") (pinfunction "1_1") (pintype "passive"))
      (node (ref "SV28") (pin "1") (pinfunction "1_1") (pintype "passive"))
    )
    (net (code "27") (name "/CV6_IN") (class "Default")
      (node (ref "DA3") (pin "3") (pinfunction "CV1_3") (pintype "input"))
      (node (ref "R14") (pin "2") (pinfunction "2_2") (pintype "passive"))
      (node (ref "R15") (pin "2") (pinfunction "2_2") (pintype "passive"))
    )
    (net (code "28") (name "/CV7") (class "Default")
      (node (ref "R20") (pin "1") (pinfunction "1_1") (pintype "passive"))
      (node (ref "SV29") (pin "1") (pinfunction "1_1") (pintype "passive"))
    )
    (net (code "29") (name "/CV8") (class "Default")
      (node (ref "R17") (pin "1") (pinfunction "1_1") (pintype "passive"))
      (node (ref "SV30") (pin "1") (pinfunction "1_1") (pintype "passive"))
    )
    (net (code "30") (name "/CV_A_DRY") (class "Default")
      (node (ref "R35") (pin "1") (pinfunction "1_1") (pintype "passive"))
      (node (ref "SV15") (pin "1") (pinfunction "1_1") (pintype "passive"))
    )
    (net (code "31") (name "/CV_A_WET") (class "Default")
      (node (ref "R32") (pin "1") (pinfunction "1_1") (pintype "passive"))
      (node (ref "SV16") (pin "1") (pinfunction "1_1") (pintype "passive"))
    )
    (net (code "32") (name "/CV_B_DRY") (class "Default")
      (node (ref "R26") (pin "1") (pinfunction "1_1") (pintype "passive"))
      (node (ref "SV17") (pin "1") (pinfunction "1_1") (pintype "passive"))
    )
    (net (code "33") (name "/CV_B_WET") (class "Default")
      (node (ref "R29") (pin "1") (pinfunction "1_1") (pintype "passive"))
      (node (ref "SV18") (pin "1") (pinfunction "1_1") (pintype "passive"))
    )
    (net (code "34") (name "/CV_O2") (class "Default")
      (node (ref "DA1") (pin "3") (pinfunction "CV1_3") (pintype "input"))
      (node (ref "R26") (pin "2") (pinfunction "2_2") (pintype "passive"))
      (node (ref "R27") (pin "2") (pinfunction "2_2") (pintype "passive"))
    )
    (net (code "35") (name "/DIG_1_BUS_A") (class "Default")
      (node (ref "IC1") (pin "4") (pinfunction "IO0_0_4") (pintype "bidirectional"))
      (node (ref "IC8") (pin "1") (pinfunction "C_1") (pintype "bidirectional"))
    )
    (net (code "36") (name "/DIG_1_BUS_B") (class "Default")
      (node (ref "IC1") (pin "5") (pinfunction "IO0_1_5") (pintype "bidirectional"))
      (node (ref "IC8") (pin "16") (pinfunction "C_16") (pintype "bidirectional"))
    )
    (net (code "37") (name "/DIG_2_BUS_A") (class "Default")
      (node (ref "IC1") (pin "6") (pinfunction "IO0_2_6") (pintype "bidirectional"))
      (node (ref "IC8") (pin "8") (pinfunction "C_8") (pintype "bidirectional"))
    )
    (net (code "38") (name "/DIG_2_BUS_B") (class "Default")
      (node (ref "IC1") (pin "7") (pinfunction "IO0_3_7") (pintype "bidirectional"))
      (node (ref "IC8") (pin "9") (pinfunction "C_9") (pintype "bidirectional"))
    )
    (net (code "39") (name "/DIG_3_BUS_A") (class "Default")
      (node (ref "IC1") (pin "17") (pinfunction "IO1_4_17") (pintype "bidirectional"))
      (node (ref "IC9") (pin "1") (pinfunction "C_1") (pintype "bidirectional"))
    )
    (net (code "40") (name "/DIG_3_BUS_B") (class "Default")
      (node (ref "IC1") (pin "18") (pinfunction "IO1_5_18") (pintype "bidirectional"))
      (node (ref "IC9") (pin "16") (pinfunction "C_16") (pintype "bidirectional"))
    )
    (net (code "41") (name "/DIG_4_BUS_A") (class "Default")
      (node (ref "IC1") (pin "19") (pinfunction "IO1_6_19") (pintype "bidirectional"))
      (node (ref "IC9") (pin "8") (pinfunction "C_8") (pintype "bidirectional"))
    )
    (net (code "42") (name "/DIG_4_BUS_B") (class "Default")
      (node (ref "IC1") (pin "20") (pinfunction "IO1_7_20") (pintype "bidirectional"))
      (node (ref "IC9") (pin "9") (pinfunction "C_9") (pintype "bidirectional"))
    )
    (net (code "43") (name "/DIG_5_BUS_A") (class "Default")
      (node (ref "IC1") (pin "15") (pinfunction "IO1_2_15") (pintype "bidirectional"))
      (node (ref "IC10") (pin "1") (pinfunction "C_1") (pintype "bidirectional"))
    )
    (net (code "44") (name "/DIG_5_BUS_B") (class "Default")
      (node (ref "IC1") (pin "16") (pinfunction "IO1_3_16") (pintype "bidirectional"))
      (node (ref "IC10") (pin "16") (pinfunction "C_16") (pintype "bidirectional"))
    )
    (net (code "45") (name "/DIG_6_BUS_A") (class "Default")
      (node (ref "IC1") (pin "13") (pinfunction "IO1_0_13") (pintype "bidirectional"))
      (node (ref "IC10") (pin "8") (pinfunction "C_8") (pintype "bidirectional"))
    )
    (net (code "46") (name "/DIG_6_BUS_B") (class "Default")
      (node (ref "IC1") (pin "14") (pinfunction "IO1_1_14") (pintype "bidirectional"))
      (node (ref "IC10") (pin "9") (pinfunction "C_9") (pintype "bidirectional"))
    )
    (net (code "47") (name "/DIG_7_BUS_A") (class "Default")
      (node (ref "IC1") (pin "8") (pinfunction "IO0_4_8") (pintype "bidirectional"))
      (node (ref "IC11") (pin "1") (pinfunction "C_1") (pintype "bidirectional"))
    )
    (net (code "48") (name "/DIG_7_BUS_B") (class "Default")
      (node (ref "IC1") (pin "9") (pinfunction "IO0_5_9") (pintype "bidirectional"))
      (node (ref "IC11") (pin "16") (pinfunction "C_16") (pintype "bidirectional"))
    )
    (net (code "49") (name "/DIG_8_BUS_A") (class "Default")
      (node (ref "IC1") (pin "10") (pinfunction "IO0_6_10") (pintype "bidirectional"))
      (node (ref "IC11") (pin "8") (pinfunction "C_8") (pintype "bidirectional"))
    )
    (net (code "50") (name "/DIG_8_BUS_B") (class "Default")
      (node (ref "IC1") (pin "11") (pinfunction "IO0_7_11") (pintype "bidirectional"))
      (node (ref "IC11") (pin "9") (pinfunction "C_9") (pintype "bidirectional"))
    )
    (net (code "51") (name "/IN1") (class "Default")
      (node (ref "R13") (pin "1") (pinfunction "1_1") (pintype "passive"))
      (node (ref "SV7") (pin "1") (pinfunction "1_1") (pintype "passive"))
    )
    (net (code "52") (name "/IN2") (class "Default")
      (node (ref "R4") (pin "1") (pinfunction "1_1") (pintype "passive"))
      (node (ref "SV8") (pin "1") (pinfunction "1_1") (pintype "passive"))
    )
    (net (code "53") (name "/IN3") (class "Default")
      (node (ref "R10") (pin "1") (pinfunction "1_1") (pintype "passive"))
      (node (ref "SV9") (pin "1") (pinfunction "1_1") (pintype "passive"))
    )
    (net (code "54") (name "/IN4") (class "Default")
      (node (ref "R7") (pin "1") (pinfunction "1_1") (pintype "passive"))
      (node (ref "SV10") (pin "1") (pinfunction "1_1") (pintype "passive"))
    )
    (net (code "55") (name "/IN5") (class "Default")
      (node (ref "R25") (pin "1") (pinfunction "1_1") (pintype "passive"))
      (node (ref "SV23") (pin "1") (pinfunction "1_1") (pintype "passive"))
    )
    (net (code "56") (name "/IN6") (class "Default")
      (node (ref "R16") (pin "1") (pinfunction "1_1") (pintype "passive"))
      (node (ref "SV24") (pin "1") (pinfunction "1_1") (pintype "passive"))
    )
    (net (code "57") (name "/IN7") (class "Default")
      (node (ref "R22") (pin "1") (pinfunction "1_1") (pintype "passive"))
      (node (ref "SV25") (pin "1") (pinfunction "1_1") (pintype "passive"))
    )
    (net (code "58") (name "/IN8") (class "Default")
      (node (ref "R19") (pin "1") (pinfunction "1_1") (pintype "passive"))
      (node (ref "SV26") (pin "1") (pinfunction "1_1") (pintype "passive"))
    )
    (net (code "59") (name "/IN_O1") (class "Default")
      (node (ref "DA1") (pin "15") (pinfunction "IN4_15") (pintype "input"))
      (node (ref "R37") (pin "2") (pinfunction "2_2") (pintype "passive"))
    )
    (net (code "60") (name "/IN_O2") (class "Default")
      (node (ref "DA1") (pin "2") (pinfunction "IN1_2") (pintype "input"))
      (node (ref "R28") (pin "2") (pinfunction "2_2") (pintype "passive"))
    )
    (net (code "61") (name "/IN_O3") (class "Default")
      (node (ref "DA1") (pin "10") (pinfunction "IN3_10") (pintype "input"))
      (node (ref "R34") (pin "2") (pinfunction "2_2") (pintype "passive"))
    )
    (net (code "62") (name "/IN_O4") (class "Default")
      (node (ref "DA1") (pin "7") (pinfunction "IN2_7") (pintype "input"))
      (node (ref "R31") (pin "2") (pinfunction "2_2") (pintype "passive"))
    )
    (net (code "63") (name "/LPF_IN_100K_MIX") (class "Default")
      (node (ref "R70") (pin "2") (pinfunction "2_2") (pintype "passive"))
      (node (ref "R72") (pin "2") (pinfunction "2_2") (pintype "passive"))
      (node (ref "SV20") (pin "1") (pinfunction "1_1") (pintype "passive"))
    )
    (net (code "64") (name "/OUT1") (class "Default")
      (node (ref "IC3") (pin "6") (pinfunction "-IN_6") (pintype "input"))
      (node (ref "IC3") (pin "7") (pinfunction "OUT_7") (pintype "output"))
      (node (ref "R59") (pin "1") (pinfunction "1_1") (pintype "passive"))
      (node (ref "R60") (pin "1") (pinfunction "1_1") (pintype "passive"))
    )
    (net (code "65") (name "/OUT2") (class "Default")
      (node (ref "IC3") (pin "1") (pinfunction "OUT_1") (pintype "output"))
      (node (ref "IC3") (pin "2") (pinfunction "-IN_2") (pintype "input"))
      (node (ref "R53") (pin "1") (pinfunction "1_1") (pintype "passive"))
      (node (ref "R54") (pin "1") (pinfunction "1_1") (pintype "passive"))
    )
    (net (code "66") (name "/OUT3") (class "Default")
      (node (ref "IC14") (pin "6") (pinfunction "-IN_6") (pintype "input"))
      (node (ref "IC14") (pin "7") (pinfunction "OUT_7") (pintype "output"))
      (node (ref "R57") (pin "1") (pinfunction "1_1") (pintype "passive"))
      (node (ref "R58") (pin "1") (pinfunction "1_1") (pintype "passive"))
    )
    (net (code "67") (name "/OUT4") (class "Default")
      (node (ref "IC14") (pin "8") (pinfunction "OUT_8") (pintype "output"))
      (node (ref "IC14") (pin "9") (pinfunction "-IN_9") (pintype "input"))
      (node (ref "R55") (pin "1") (pinfunction "1_1") (pintype "passive"))
      (node (ref "R56") (pin "1") (pinfunction "1_1") (pintype "passive"))
    )
    (net (code "68") (name "/OUT5") (class "Default")
      (node (ref "IC2") (pin "1") (pinfunction "OUT_1") (pintype "output"))
      (node (ref "IC2") (pin "2") (pinfunction "-IN_2") (pintype "input"))
      (node (ref "R67") (pin "1") (pinfunction "1_1") (pintype "passive"))
      (node (ref "R68") (pin "1") (pinfunction "1_1") (pintype "passive"))
    )
    (net (code "69") (name "/OUT6") (class "Default")
      (node (ref "IC2") (pin "13") (pinfunction "-IN_13") (pintype "input"))
      (node (ref "IC2") (pin "14") (pinfunction "OUT_14") (pintype "output"))
      (node (ref "R61") (pin "1") (pinfunction "1_1") (pintype "passive"))
      (node (ref "R62") (pin "1") (pinfunction "1_1") (pintype "passive"))
    )
    (net (code "70") (name "/OUT7") (class "Default")
      (node (ref "IC6") (pin "6") (pinfunction "-IN_6") (pintype "input"))
      (node (ref "IC6") (pin "7") (pinfunction "OUT_7") (pintype "output"))
      (node (ref "R65") (pin "1") (pinfunction "1_1") (pintype "passive"))
      (node (ref "R66") (pin "1") (pinfunction "1_1") (pintype "passive"))
    )
    (net (code "71") (name "/OUT8") (class "Default")
      (node (ref "IC6") (pin "1") (pinfunction "OUT_1") (pintype "output"))
      (node (ref "IC6") (pin "2") (pinfunction "-IN_2") (pintype "input"))
      (node (ref "R63") (pin "1") (pinfunction "1_1") (pintype "passive"))
      (node (ref "R64") (pin "1") (pinfunction "1_1") (pintype "passive"))
    )
    (net (code "72") (name "/OUT_A") (class "Default")
      (node (ref "IC14") (pin "1") (pinfunction "OUT_1") (pintype "output"))
      (node (ref "IC14") (pin "2") (pinfunction "-IN_2") (pintype "input"))
      (node (ref "R69") (pin "1") (pinfunction "1_1") (pintype "passive"))
    )
    (net (code "73") (name "/OUT_B") (class "Default")
      (node (ref "IC14") (pin "13") (pinfunction "-IN_13") (pintype "input"))
      (node (ref "IC14") (pin "14") (pinfunction "OUT_14") (pintype "output"))
      (node (ref "R70") (pin "1") (pinfunction "1_1") (pintype "passive"))
    )
    (net (code "74") (name "/OUT_FX_A") (class "Default")
      (node (ref "IC2") (pin "6") (pinfunction "-IN_6") (pintype "input"))
      (node (ref "IC2") (pin "7") (pinfunction "OUT_7") (pintype "output"))
      (node (ref "R71") (pin "1") (pinfunction "1_1") (pintype "passive"))
    )
    (net (code "75") (name "/OUT_FX_B") (class "Default")
      (node (ref "IC2") (pin "8") (pinfunction "OUT_8") (pintype "output"))
      (node (ref "IC2") (pin "9") (pinfunction "-IN_9") (pintype "input"))
      (node (ref "R72") (pin "1") (pinfunction "1_1") (pintype "passive"))
    )
    (net (code "76") (name "/SCL") (class "Default")
      (node (ref "IC1") (pin "22") (pinfunction "SCL_22") (pintype "bidirectional"))
      (node (ref "SV4") (pin "1") (pinfunction "1_1") (pintype "passive"))
    )
    (net (code "77") (name "/SDA") (class "Default")
      (node (ref "IC1") (pin "23") (pinfunction "SDA_23") (pintype "bidirectional"))
      (node (ref "SV3") (pin "1") (pinfunction "1_1") (pintype "passive"))
    )
    (net (code "78") (name "/SUM1") (class "Default")
      (node (ref "DA2") (pin "15") (pinfunction "IN4_15") (pintype "input"))
      (node (ref "R13") (pin "2") (pinfunction "2_2") (pintype "passive"))
    )
    (net (code "79") (name "/SUM2") (class "Default")
      (node (ref "DA2") (pin "2") (pinfunction "IN1_2") (pintype "input"))
      (node (ref "R4") (pin "2") (pinfunction "2_2") (pintype "passive"))
    )
    (net (code "80") (name "/SUM3") (class "Default")
      (node (ref "DA2") (pin "10") (pinfunction "IN3_10") (pintype "input"))
      (node (ref "R10") (pin "2") (pinfunction "2_2") (pintype "passive"))
    )
    (net (code "81") (name "/SUM4") (class "Default")
      (node (ref "DA2") (pin "7") (pinfunction "IN2_7") (pintype "input"))
      (node (ref "R7") (pin "2") (pinfunction "2_2") (pintype "passive"))
    )
    (net (code "82") (name "/SUM5") (class "Default")
      (node (ref "DA3") (pin "15") (pinfunction "IN4_15") (pintype "input"))
      (node (ref "R25") (pin "2") (pinfunction "2_2") (pintype "passive"))
    )
    (net (code "83") (name "/SUM6") (class "Default")
      (node (ref "DA3") (pin "2") (pinfunction "IN1_2") (pintype "input"))
      (node (ref "R16") (pin "2") (pinfunction "2_2") (pintype "passive"))
    )
    (net (code "84") (name "/SUM7") (class "Default")
      (node (ref "DA3") (pin "10") (pinfunction "IN3_10") (pintype "input"))
      (node (ref "R22") (pin "2") (pinfunction "2_2") (pintype "passive"))
    )
    (net (code "85") (name "/SUM8") (class "Default")
      (node (ref "DA3") (pin "7") (pinfunction "IN2_7") (pintype "input"))
      (node (ref "R19") (pin "2") (pinfunction "2_2") (pintype "passive"))
    )
    (net (code "86") (name "/SUM_A") (class "Default")
      (node (ref "IC4") (pin "1") (pinfunction "OUT_1") (pintype "output"))
      (node (ref "R37") (pin "1") (pinfunction "1_1") (pintype "passive"))
      (node (ref "R79") (pin "2") (pinfunction "2_2") (pintype "passive"))
    )
    (net (code "87") (name "/SUM_B") (class "Default")
      (node (ref "IC4") (pin "14") (pinfunction "OUT_14") (pintype "output"))
      (node (ref "R28") (pin "1") (pinfunction "1_1") (pintype "passive"))
      (node (ref "R80") (pin "2") (pinfunction "2_2") (pintype "passive"))
    )
    (net (code "88") (name "/SUM_FX_A") (class "Default")
      (node (ref "IC4") (pin "7") (pinfunction "OUT_7") (pintype "output"))
      (node (ref "R34") (pin "1") (pinfunction "1_1") (pintype "passive"))
      (node (ref "R81") (pin "2") (pinfunction "2_2") (pintype "passive"))
    )
    (net (code "89") (name "/SUM_FX_B") (class "Default")
      (node (ref "IC4") (pin "8") (pinfunction "OUT_8") (pintype "output"))
      (node (ref "R31") (pin "1") (pinfunction "1_1") (pintype "passive"))
      (node (ref "R82") (pin "2") (pinfunction "2_2") (pintype "passive"))
    )
    (net (code "90") (name "/SVF_IN_100K_MIX") (class "Default")
      (node (ref "R69") (pin "2") (pinfunction "2_2") (pintype "passive"))
      (node (ref "R71") (pin "2") (pinfunction "2_2") (pintype "passive"))
      (node (ref "SV19") (pin "1") (pinfunction "1_1") (pintype "passive"))
    )
    (net (code "91") (name "/SW1A") (class "Default")
      (node (ref "IC8") (pin "2") (pinfunction "D_2") (pintype "bidirectional"))
      (node (ref "R59") (pin "2") (pinfunction "2_2") (pintype "passive"))
    )
    (net (code "92") (name "/SW1B") (class "Default")
      (node (ref "IC8") (pin "15") (pinfunction "D_15") (pintype "bidirectional"))
      (node (ref "R60") (pin "2") (pinfunction "2_2") (pintype "passive"))
    )
    (net (code "93") (name "/SW2A") (class "Default")
      (node (ref "IC8") (pin "7") (pinfunction "D_7") (pintype "bidirectional"))
      (node (ref "R53") (pin "2") (pinfunction "2_2") (pintype "passive"))
    )
    (net (code "94") (name "/SW2B") (class "Default")
      (node (ref "IC8") (pin "10") (pinfunction "D_10") (pintype "bidirectional"))
      (node (ref "R54") (pin "2") (pinfunction "2_2") (pintype "passive"))
    )
    (net (code "95") (name "/SW3A") (class "Default")
      (node (ref "IC9") (pin "2") (pinfunction "D_2") (pintype "bidirectional"))
      (node (ref "R57") (pin "2") (pinfunction "2_2") (pintype "passive"))
    )
    (net (code "96") (name "/SW3B") (class "Default")
      (node (ref "IC9") (pin "15") (pinfunction "D_15") (pintype "bidirectional"))
      (node (ref "R58") (pin "2") (pinfunction "2_2") (pintype "passive"))
    )
    (net (code "97") (name "/SW4A") (class "Default")
      (node (ref "IC9") (pin "7") (pinfunction "D_7") (pintype "bidirectional"))
      (node (ref "R55") (pin "2") (pinfunction "2_2") (pintype "passive"))
    )
    (net (code "98") (name "/SW4B") (class "Default")
      (node (ref "IC9") (pin "10") (pinfunction "D_10") (pintype "bidirectional"))
      (node (ref "R56") (pin "2") (pinfunction "2_2") (pintype "passive"))
    )
    (net (code "99") (name "/SW5A") (class "Default")
      (node (ref "IC10") (pin "2") (pinfunction "D_2") (pintype "bidirectional"))
      (node (ref "R67") (pin "2") (pinfunction "2_2") (pintype "passive"))
    )
    (net (code "100") (name "/SW5B") (class "Default")
      (node (ref "IC10") (pin "15") (pinfunction "D_15") (pintype "bidirectional"))
      (node (ref "R68") (pin "2") (pinfunction "2_2") (pintype "passive"))
    )
    (net (code "101") (name "/SW6A") (class "Default")
      (node (ref "IC10") (pin "7") (pinfunction "D_7") (pintype "bidirectional"))
      (node (ref "R61") (pin "2") (pinfunction "2_2") (pintype "passive"))
    )
    (net (code "102") (name "/SW6B") (class "Default")
      (node (ref "IC10") (pin "10") (pinfunction "D_10") (pintype "bidirectional"))
      (node (ref "R62") (pin "2") (pinfunction "2_2") (pintype "passive"))
    )
    (net (code "103") (name "/SW7A") (class "Default")
      (node (ref "IC11") (pin "2") (pinfunction "D_2") (pintype "bidirectional"))
      (node (ref "R65") (pin "2") (pinfunction "2_2") (pintype "passive"))
    )
    (net (code "104") (name "/SW7B") (class "Default")
      (node (ref "IC11") (pin "15") (pinfunction "D_15") (pintype "bidirectional"))
      (node (ref "R66") (pin "2") (pinfunction "2_2") (pintype "passive"))
    )
    (net (code "105") (name "/SW8A") (class "Default")
      (node (ref "IC11") (pin "7") (pinfunction "D_7") (pintype "bidirectional"))
      (node (ref "R63") (pin "2") (pinfunction "2_2") (pintype "passive"))
    )
    (net (code "106") (name "/SW8B") (class "Default")
      (node (ref "IC11") (pin "10") (pinfunction "D_10") (pintype "bidirectional"))
      (node (ref "R64") (pin "2") (pinfunction "2_2") (pintype "passive"))
    )
    (net (code "107") (name "/VL") (class "Default")
      (node (ref "IC10") (pin "12") (pinfunction "VL_12") (pintype "bidirectional"))
      (node (ref "IC11") (pin "12") (pinfunction "VL_12") (pintype "bidirectional"))
      (node (ref "IC8") (pin "12") (pinfunction "VL_12") (pintype "bidirectional"))
      (node (ref "IC9") (pin "12") (pinfunction "VL_12") (pintype "bidirectional"))
      (node (ref "R77") (pin "2") (pinfunction "2_2") (pintype "passive"))
      (node (ref "R78") (pin "1") (pinfunction "1_1") (pintype "passive"))
    )
    (net (code "108") (name "/~{RST}") (class "Default")
      (node (ref "IC1") (pin "3") (pinfunction "~{RESET}_3") (pintype "bidirectional"))
      (node (ref "R1") (pin "2") (pinfunction "2_2") (pintype "passive"))
      (node (ref "SV6") (pin "1") (pinfunction "1_1") (pintype "passive"))
    )
    (net (code "109") (name "DGND") (class "Default")
      (node (ref "C23") (pin "1") (pinfunction "1_1") (pintype "passive"))
      (node (ref "IC1") (pin "12") (pinfunction "VSS_12") (pintype "power_in"))
      (node (ref "IC1") (pin "2") (pinfunction "A1_2") (pintype "bidirectional"))
      (node (ref "IC1") (pin "21") (pinfunction "A0_21") (pintype "bidirectional"))
      (node (ref "SV5") (pin "1") (pinfunction "1_1") (pintype "passive"))
    )
    (net (code "110") (name "GND") (class "Default")
      (node (ref "C1") (pin "1") (pinfunction "1_1") (pintype "passive"))
      (node (ref "C10") (pin "2") (pinfunction "2_2") (pintype "passive"))
      (node (ref "C11") (pin "1") (pinfunction "1_1") (pintype "passive"))
      (node (ref "C12") (pin "2") (pinfunction "2_2") (pintype "passive"))
      (node (ref "C13") (pin "1") (pinfunction "1_1") (pintype "passive"))
      (node (ref "C14") (pin "1") (pinfunction "1_1") (pintype "passive"))
      (node (ref "C15") (pin "1") (pinfunction "1_1") (pintype "passive"))
      (node (ref "C16") (pin "1") (pinfunction "1_1") (pintype "passive"))
      (node (ref "C17") (pin "2") (pinfunction "2_2") (pintype "passive"))
      (node (ref "C2") (pin "2") (pinfunction "2_2") (pintype "passive"))
      (node (ref "C3") (pin "1") (pinfunction "1_1") (pintype "passive"))
      (node (ref "C4") (pin "2") (pinfunction "2_2") (pintype "passive"))
      (node (ref "C5") (pin "1") (pinfunction "1_1") (pintype "passive"))
      (node (ref "C6") (pin "2") (pinfunction "2_2") (pintype "passive"))
      (node (ref "C7") (pin "1") (pinfunction "1_1") (pintype "passive"))
      (node (ref "C8") (pin "2") (pinfunction "2_2") (pintype "passive"))
      (node (ref "C9") (pin "1") (pinfunction "1_1") (pintype "passive"))
      (node (ref "DA1") (pin "8") (pinfunction "GND_8") (pintype "power_in"))
      (node (ref "DA2") (pin "8") (pinfunction "GND_8") (pintype "power_in"))
      (node (ref "DA3") (pin "8") (pinfunction "GND_8") (pintype "power_in"))
      (node (ref "IC10") (pin "5") (pinfunction "AGND_5") (pintype "power_in"))
      (node (ref "IC11") (pin "5") (pinfunction "AGND_5") (pintype "power_in"))
      (node (ref "IC4") (pin "10") (pinfunction "+IN_10") (pintype "input"))
      (node (ref "IC4") (pin "12") (pinfunction "+IN_12") (pintype "input"))
      (node (ref "IC4") (pin "3") (pinfunction "+IN_3") (pintype "input"))
      (node (ref "IC4") (pin "5") (pinfunction "+IN_5") (pintype "input"))
      (node (ref "IC8") (pin "5") (pinfunction "AGND_5") (pintype "power_in"))
      (node (ref "IC9") (pin "5") (pinfunction "AGND_5") (pintype "power_in"))
      (node (ref "R12") (pin "1") (pinfunction "1_1") (pintype "passive"))
      (node (ref "R15") (pin "1") (pinfunction "1_1") (pintype "passive"))
      (node (ref "R18") (pin "1") (pinfunction "1_1") (pintype "passive"))
      (node (ref "R21") (pin "1") (pinfunction "1_1") (pintype "passive"))
      (node (ref "R24") (pin "1") (pinfunction "1_1") (pintype "passive"))
      (node (ref "R27") (pin "1") (pinfunction "1_1") (pintype "passive"))
      (node (ref "R3") (pin "1") (pinfunction "1_1") (pintype "passive"))
      (node (ref "R30") (pin "1") (pinfunction "1_1") (pintype "passive"))
      (node (ref "R33") (pin "1") (pinfunction "1_1") (pintype "passive"))
      (node (ref "R36") (pin "1") (pinfunction "1_1") (pintype "passive"))
      (node (ref "R41") (pin "1") (pinfunction "1_1") (pintype "passive"))
      (node (ref "R42") (pin "1") (pinfunction "1_1") (pintype "passive"))
      (node (ref "R43") (pin "1") (pinfunction "1_1") (pintype "passive"))
      (node (ref "R44") (pin "1") (pinfunction "1_1") (pintype "passive"))
      (node (ref "R45") (pin "1") (pinfunction "1_1") (pintype "passive"))
      (node (ref "R46") (pin "1") (pinfunction "1_1") (pintype "passive"))
      (node (ref "R47") (pin "1") (pinfunction "1_1") (pintype "passive"))
      (node (ref "R48") (pin "1") (pinfunction "1_1") (pintype "passive"))
      (node (ref "R49") (pin "1") (pinfunction "1_1") (pintype "passive"))
      (node (ref "R50") (pin "1") (pinfunction "1_1") (pintype "passive"))
      (node (ref "R51") (pin "1") (pinfunction "1_1") (pintype "passive"))
      (node (ref "R52") (pin "1") (pinfunction "1_1") (pintype "passive"))
      (node (ref "R6") (pin "1") (pinfunction "1_1") (pintype "passive"))
      (node (ref "R73") (pin "1") (pinfunction "1_1") (pintype "passive"))
      (node (ref "R74") (pin "1") (pinfunction "1_1") (pintype "passive"))
      (node (ref "R75") (pin "1") (pinfunction "1_1") (pintype "passive"))
      (node (ref "R76") (pin "1") (pinfunction "1_1") (pintype "passive"))
      (node (ref "R78") (pin "2") (pinfunction "2_2") (pintype "passive"))
      (node (ref "R9") (pin "1") (pinfunction "1_1") (pintype "passive"))
      (node (ref "SV22") (pin "1") (pinfunction "1_1") (pintype "passive"))
    )
    (net (code "111") (name "Net-(C13-Pad2)") (class "Default")
      (node (ref "C13") (pin "2") (pinfunction "2_2") (pintype "passive"))
      (node (ref "R38") (pin "1") (pinfunction "1_1") (pintype "passive"))
    )
    (net (code "112") (name "Net-(C14-Pad2)") (class "Default")
      (node (ref "C14") (pin "2") (pinfunction "2_2") (pintype "passive"))
      (node (ref "R39") (pin "1") (pinfunction "1_1") (pintype "passive"))
    )
    (net (code "113") (name "Net-(C15-Pad2)") (class "Default")
      (node (ref "C15") (pin "2") (pinfunction "2_2") (pintype "passive"))
      (node (ref "R40") (pin "1") (pinfunction "1_1") (pintype "passive"))
    )
    (net (code "114") (name "Net-(DA1B-CV2)") (class "Default")
      (node (ref "DA1") (pin "6") (pinfunction "CV2_6") (pintype "input"))
      (node (ref "R29") (pin "2") (pinfunction "2_2") (pintype "passive"))
      (node (ref "R30") (pin "2") (pinfunction "2_2") (pintype "passive"))
    )
    (net (code "115") (name "Net-(DA1B-CV3)") (class "Default")
      (node (ref "DA1") (pin "11") (pinfunction "CV3_11") (pintype "input"))
      (node (ref "R32") (pin "2") (pinfunction "2_2") (pintype "passive"))
      (node (ref "R33") (pin "2") (pinfunction "2_2") (pintype "passive"))
    )
    (net (code "116") (name "Net-(DA1B-CV4)") (class "Default")
      (node (ref "DA1") (pin "14") (pinfunction "CV4_14") (pintype "input"))
      (node (ref "R35") (pin "2") (pinfunction "2_2") (pintype "passive"))
      (node (ref "R36") (pin "2") (pinfunction "2_2") (pintype "passive"))
    )
    (net (code "117") (name "Net-(DA1B-VREF)") (class "Default")
      (node (ref "DA1") (pin "1") (pinfunction "VREF_1") (pintype "output"))
      (node (ref "R40") (pin "2") (pinfunction "2_2") (pintype "passive"))
    )
    (net (code "118") (name "Net-(DA2B-CV2)") (class "Default")
      (node (ref "DA2") (pin "6") (pinfunction "CV2_6") (pintype "input"))
      (node (ref "R5") (pin "2") (pinfunction "2_2") (pintype "passive"))
      (node (ref "R6") (pin "2") (pinfunction "2_2") (pintype "passive"))
    )
    (net (code "119") (name "Net-(DA2B-CV3)") (class "Default")
      (node (ref "DA2") (pin "11") (pinfunction "CV3_11") (pintype "input"))
      (node (ref "R8") (pin "2") (pinfunction "2_2") (pintype "passive"))
      (node (ref "R9") (pin "2") (pinfunction "2_2") (pintype "passive"))
    )
    (net (code "120") (name "Net-(DA2B-CV4)") (class "Default")
      (node (ref "DA2") (pin "14") (pinfunction "CV4_14") (pintype "input"))
      (node (ref "R11") (pin "2") (pinfunction "2_2") (pintype "passive"))
      (node (ref "R12") (pin "2") (pinfunction "2_2") (pintype "passive"))
    )
    (net (code "121") (name "Net-(DA2B-VREF)") (class "Default")
      (node (ref "DA2") (pin "1") (pinfunction "VREF_1") (pintype "output"))
      (node (ref "R38") (pin "2") (pinfunction "2_2") (pintype "passive"))
    )
    (net (code "122") (name "Net-(DA3B-CV2)") (class "Default")
      (node (ref "DA3") (pin "6") (pinfunction "CV2_6") (pintype "input"))
      (node (ref "R17") (pin "2") (pinfunction "2_2") (pintype "passive"))
      (node (ref "R18") (pin "2") (pinfunction "2_2") (pintype "passive"))
    )
    (net (code "123") (name "Net-(DA3B-CV3)") (class "Default")
      (node (ref "DA3") (pin "11") (pinfunction "CV3_11") (pintype "input"))
      (node (ref "R20") (pin "2") (pinfunction "2_2") (pintype "passive"))
      (node (ref "R21") (pin "2") (pinfunction "2_2") (pintype "passive"))
    )
    (net (code "124") (name "Net-(DA3B-CV4)") (class "Default")
      (node (ref "DA3") (pin "14") (pinfunction "CV4_14") (pintype "input"))
      (node (ref "R23") (pin "2") (pinfunction "2_2") (pintype "passive"))
      (node (ref "R24") (pin "2") (pinfunction "2_2") (pintype "passive"))
    )
    (net (code "125") (name "Net-(DA3B-VREF)") (class "Default")
      (node (ref "DA3") (pin "1") (pinfunction "VREF_1") (pintype "output"))
      (node (ref "R39") (pin "2") (pinfunction "2_2") (pintype "passive"))
    )
    (net (code "126") (name "unconnected-(IC1-~{INT}-Pad1)") (class "Default")
      (node (ref "IC1") (pin "1") (pinfunction "~{INT}_1") (pintype "bidirectional"))
    )
    (net (code "127") (name "unconnected-(SV1-Pad1)") (class "Default")
      (node (ref "SV1") (pin "1") (pinfunction "1_1") (pintype "passive"))
    )
    (net (code "128") (name "unconnected-(SV32-Pad1)") (class "Default")
      (node (ref "SV32") (pin "1") (pinfunction "1_1") (pintype "passive"))
    )
  )
)
